# Y_Stepper_Motor_Driver.net
KiCad netlist of a schematic drawn in Altium Designer
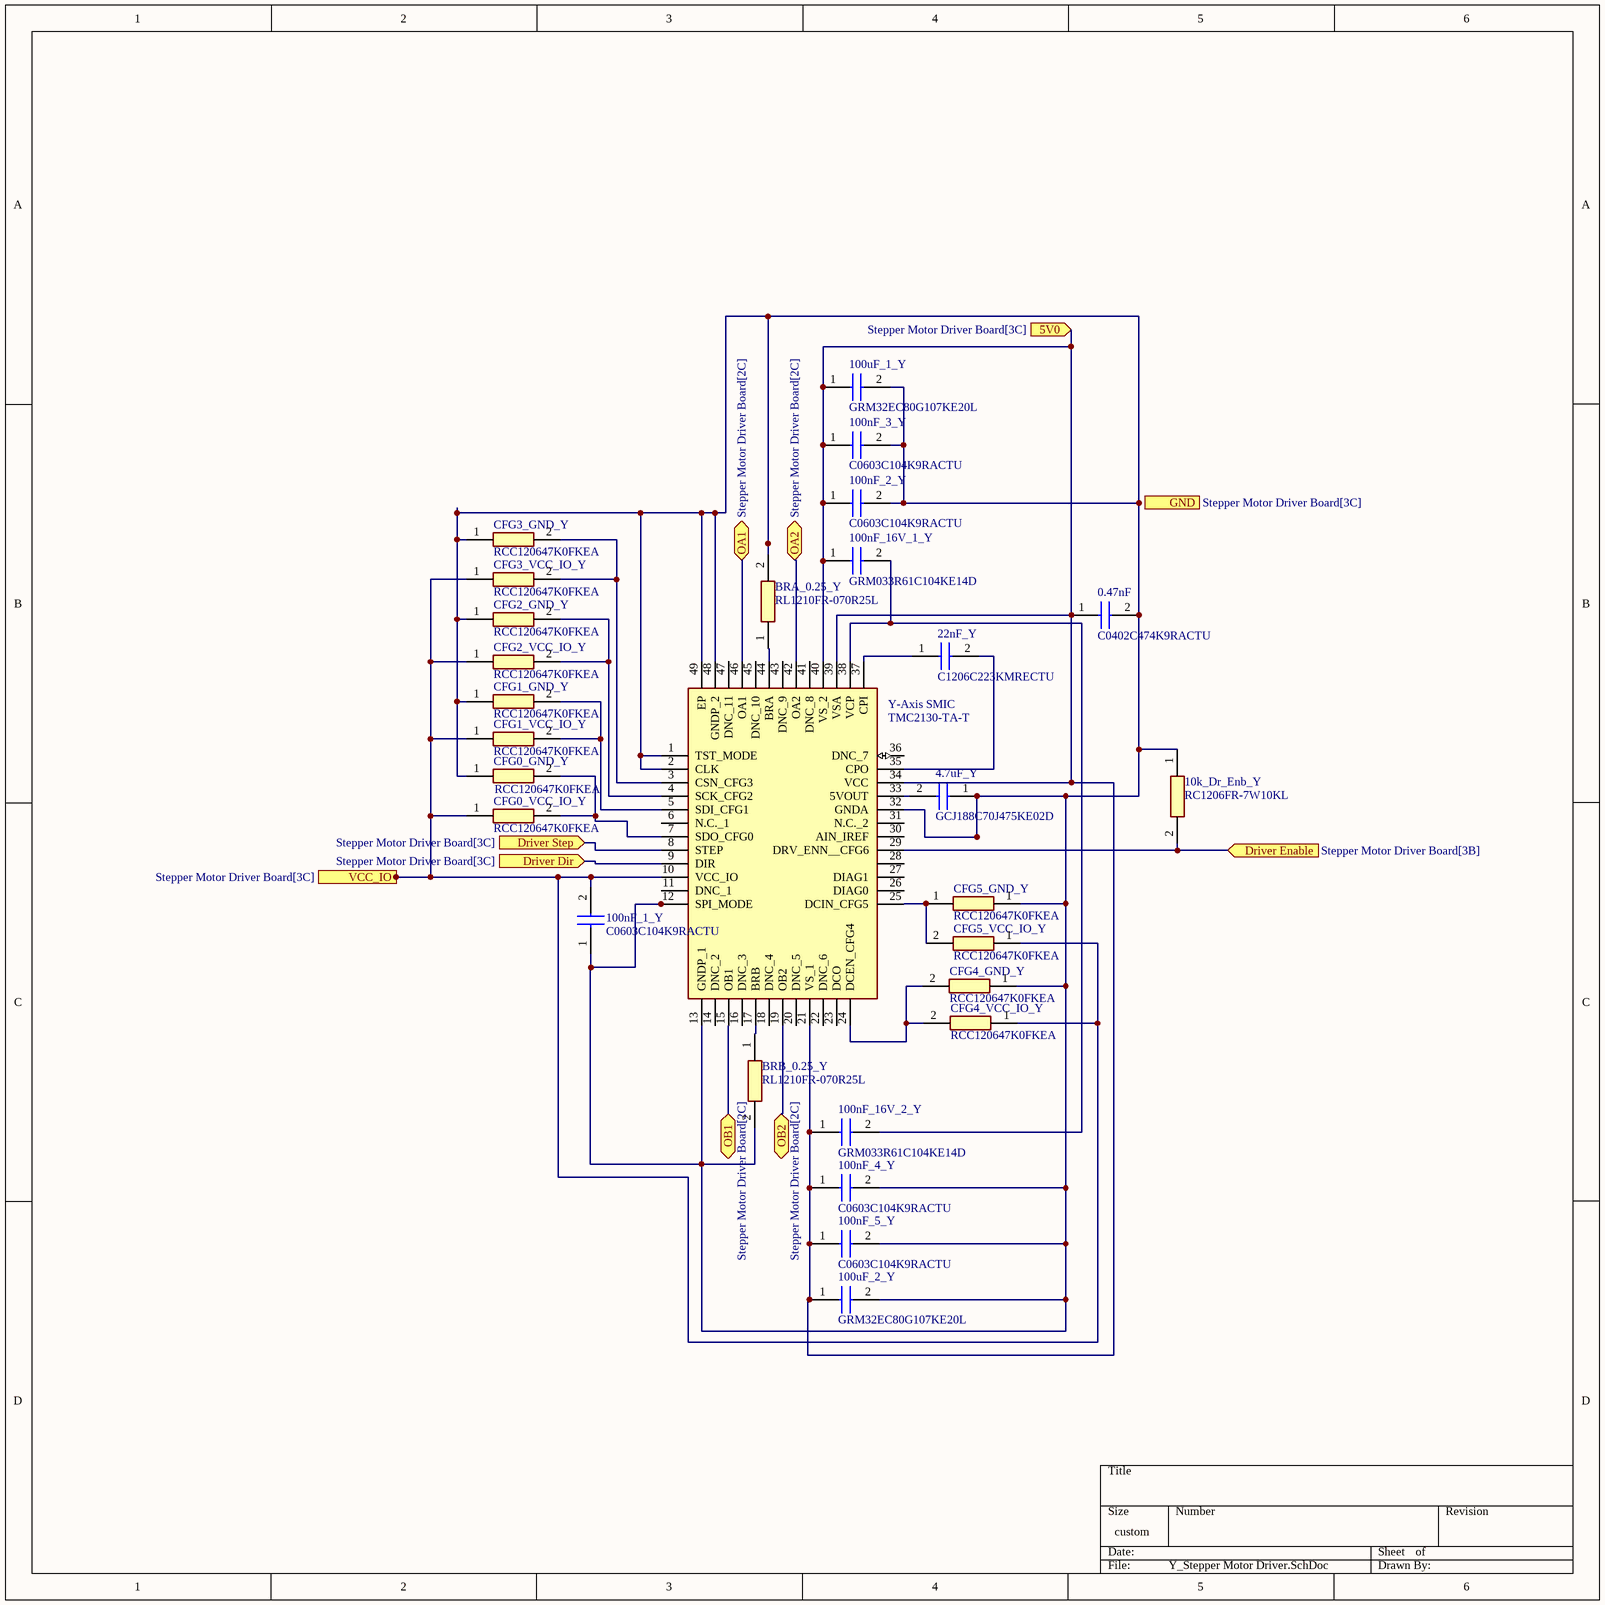
[diagram p0: Y_Stepper Motor Driver.SchDoc]

(export (version "E")
  (design (tool "Eeschema 10.0.6"))
  (components
    (comp (ref "0.47nF")
      (value "C0402C474K9RACTU")
      (footprint "SamacSys:CAPC1005X55N")
      (description "Capacitor")
      (fields (field (name "MOUSER PART NUMBER") "80-C0402C474K9RACTU"))
      (libsource (lib "*") (part "C0402C474K9RACTU"))
    )
    (comp (ref "4.7uF_Y")
      (value "GCJ188C70J475KE02D")
      (footprint "SamacSys:CAPC1608X100N")
      (description "Capacitor")
      (fields (field (name "MOUSER PART NUMBER") "81-GCJ188C70J475KE2D"))
      (libsource (lib "*") (part "GCJ188C70J475KE02D"))
    )
    (comp (ref "10k_Dr_Enb_Y")
      (value "RC1206FR-7W10KL")
      (footprint "SamacSys:RESC3116X65N")
      (description "Resistor")
      (libsource (lib "*") (part "RC1206FR-7W10KL"))
    )
    (comp (ref "22nF_Y")
      (value "C1206C223KMRECTU")
      (footprint "SamacSys:C1206")
      (description "Capacitor")
      (fields (field (name "MOUSER PART NUMBER") "80-C1206C223KMRECTU"))
      (libsource (lib "*") (part "C1206C223KMRECTU"))
    )
    (comp (ref "100nF_1_Y")
      (value "C0603C104K9RACTU")
      (footprint "SamacSys:C0603")
      (description "Capacitor")
      (fields (field (name "MOUSER PART NUMBER") "80-C0603C104K9R"))
      (libsource (lib "*") (part "C0603C104K9RACTU"))
    )
    (comp (ref "100nF_2_Y")
      (value "C0603C104K9RACTU")
      (footprint "SamacSys:C0603")
      (description "Capacitor")
      (fields (field (name "MOUSER PART NUMBER") "80-C0603C104K9R"))
      (libsource (lib "*") (part "C0603C104K9RACTU"))
    )
    (comp (ref "100nF_3_Y")
      (value "C0603C104K9RACTU")
      (footprint "SamacSys:C0603")
      (description "Capacitor")
      (fields (field (name "MOUSER PART NUMBER") "80-C0603C104K9R"))
      (libsource (lib "*") (part "C0603C104K9RACTU"))
    )
    (comp (ref "100nF_4_Y")
      (value "C0603C104K9RACTU")
      (footprint "SamacSys:C0603")
      (description "Capacitor")
      (fields (field (name "MOUSER PART NUMBER") "80-C0603C104K9R"))
      (libsource (lib "*") (part "C0603C104K9RACTU"))
    )
    (comp (ref "100nF_5_Y")
      (value "C0603C104K9RACTU")
      (footprint "SamacSys:C0603")
      (description "Capacitor")
      (fields (field (name "MOUSER PART NUMBER") "80-C0603C104K9R"))
      (libsource (lib "*") (part "C0603C104K9RACTU"))
    )
    (comp (ref "100nF_16V_1_Y")
      (value "GRM033R61C104KE14D")
      (footprint "SamacSys:CAPC0603X33N")
      (description "Capacitor")
      (fields (field (name "MOUSER PART NUMBER") "81-GRM033R61C104KE4D"))
      (libsource (lib "*") (part "GRM033R61C104KE14D"))
    )
    (comp (ref "100nF_16V_2_Y")
      (value "GRM033R61C104KE14D")
      (footprint "SamacSys:CAPC0603X33N")
      (description "Capacitor")
      (fields (field (name "MOUSER PART NUMBER") "81-GRM033R61C104KE4D"))
      (libsource (lib "*") (part "GRM033R61C104KE14D"))
    )
    (comp (ref "100uF_1_Y")
      (value "GRM32EC80G107KE20L")
      (footprint "SamacSys:CAPC3225X270N")
      (description "Capacitor")
      (fields (field (name "MOUSER PART NUMBER") "81-GRM32EC80G107KE0L"))
      (libsource (lib "*") (part "GRM32EC80G107KE20L"))
    )
    (comp (ref "100uF_2_Y")
      (value "GRM32EC80G107KE20L")
      (footprint "SamacSys:CAPC3225X270N")
      (description "Capacitor")
      (fields (field (name "MOUSER PART NUMBER") "81-GRM32EC80G107KE0L"))
      (libsource (lib "*") (part "GRM32EC80G107KE20L"))
    )
    (comp (ref "BRA_0.25_Y")
      (value "RL1210FR-070R25L")
      (footprint "SamacSys:RESC3126X65N")
      (description "Resistor")
      (fields (field (name "MOUSER PART NUMBER") "603-RL1210FR-070R25L"))
      (libsource (lib "") (part "RL1210FR-070R25L_1"))
    )
    (comp (ref "BRB_0.25_Y")
      (value "RL1210FR-070R25L")
      (footprint "SamacSys:RESC3126X65N")
      (description "Resistor")
      (fields (field (name "MOUSER PART NUMBER") "603-RL1210FR-070R25L"))
      (libsource (lib "*") (part "RL1210FR-070R25L"))
    )
    (comp (ref "CFG0_GND_Y")
      (value "RCC120647K0FKEA")
      (footprint "SamacSys:RCC1206_e3")
      (description "Resistor")
      (fields (field (name "MOUSER PART NUMBER") "71-RCC120647K0FKEA"))
      (libsource (lib "*") (part "RCC120647K0FKEA"))
    )
    (comp (ref "CFG0_VCC_IO_Y")
      (value "RCC120647K0FKEA")
      (footprint "SamacSys:RCC1206_e3")
      (description "Resistor")
      (fields (field (name "MOUSER PART NUMBER") "71-RCC120647K0FKEA"))
      (libsource (lib "*") (part "RCC120647K0FKEA"))
    )
    (comp (ref "CFG1_GND_Y")
      (value "RCC120647K0FKEA")
      (footprint "SamacSys:RCC1206_e3")
      (description "Resistor")
      (fields (field (name "MOUSER PART NUMBER") "71-RCC120647K0FKEA"))
      (libsource (lib "*") (part "RCC120647K0FKEA"))
    )
    (comp (ref "CFG1_VCC_IO_Y")
      (value "RCC120647K0FKEA")
      (footprint "SamacSys:RCC1206_e3")
      (description "Resistor")
      (fields (field (name "MOUSER PART NUMBER") "71-RCC120647K0FKEA"))
      (libsource (lib "*") (part "RCC120647K0FKEA"))
    )
    (comp (ref "CFG2_GND_Y")
      (value "RCC120647K0FKEA")
      (footprint "SamacSys:RCC1206_e3")
      (description "Resistor")
      (fields (field (name "MOUSER PART NUMBER") "71-RCC120647K0FKEA"))
      (libsource (lib "*") (part "RCC120647K0FKEA"))
    )
    (comp (ref "CFG2_VCC_IO_Y")
      (value "RCC120647K0FKEA")
      (footprint "SamacSys:RCC1206_e3")
      (description "Resistor")
      (fields (field (name "MOUSER PART NUMBER") "71-RCC120647K0FKEA"))
      (libsource (lib "*") (part "RCC120647K0FKEA"))
    )
    (comp (ref "CFG3_GND_Y")
      (value "RCC120647K0FKEA")
      (footprint "SamacSys:RCC1206_e3")
      (description "Resistor")
      (fields (field (name "MOUSER PART NUMBER") "71-RCC120647K0FKEA"))
      (libsource (lib "*") (part "RCC120647K0FKEA"))
    )
    (comp (ref "CFG3_VCC_IO_Y")
      (value "RCC120647K0FKEA")
      (footprint "SamacSys:RCC1206_e3")
      (description "Resistor")
      (fields (field (name "MOUSER PART NUMBER") "71-RCC120647K0FKEA"))
      (libsource (lib "*") (part "RCC120647K0FKEA"))
    )
    (comp (ref "CFG4_GND_Y")
      (value "RCC120647K0FKEA")
      (footprint "SamacSys:RCC1206_e3")
      (description "Resistor")
      (fields (field (name "MOUSER PART NUMBER") "71-RCC120647K0FKEA"))
      (libsource (lib "") (part "RCC120647K0FKEA_1"))
    )
    (comp (ref "CFG4_VCC_IO_Y")
      (value "RCC120647K0FKEA")
      (footprint "SamacSys:RCC1206_e3")
      (description "Resistor")
      (fields (field (name "MOUSER PART NUMBER") "71-RCC120647K0FKEA"))
      (libsource (lib "") (part "RCC120647K0FKEA_1"))
    )
    (comp (ref "CFG5_GND_Y")
      (value "RCC120647K0FKEA")
      (footprint "SamacSys:RCC1206_e3")
      (description "Resistor")
      (fields (field (name "MOUSER PART NUMBER") "71-RCC120647K0FKEA"))
      (libsource (lib "") (part "RCC120647K0FKEA_2"))
    )
    (comp (ref "CFG5_VCC_IO_Y")
      (value "RCC120647K0FKEA")
      (footprint "SamacSys:RCC1206_e3")
      (description "Resistor")
      (fields (field (name "MOUSER PART NUMBER") "71-RCC120647K0FKEA"))
      (libsource (lib "") (part "RCC120647K0FKEA_1"))
    )
    (comp (ref "Y-Axis SMIC")
      (value "TMC2130-TA-T")
      (footprint "SamacSys:QFP50P900X900X120-49N")
      (description "Integrated Circuit")
      (fields (field (name "MOUSER PART NUMBER") "700-TMC2130-TA-T"))
      (libsource (lib "*") (part "TMC2130-TA-T"))
    )
  )
  (nets
    (net (code "1") (name "/5V0") (class "Default")
      (node (ref "0.47nF") (pin "1") (pinfunction "1_1") (pintype "passive"))
      (node (ref "100nF_16V_1_Y") (pin "1") (pinfunction "1_1") (pintype "passive"))
      (node (ref "100nF_16V_2_Y") (pin "1") (pinfunction "1_1") (pintype "passive"))
      (node (ref "100nF_2_Y") (pin "1") (pinfunction "1_1") (pintype "passive"))
      (node (ref "100nF_3_Y") (pin "1") (pinfunction "1_1") (pintype "passive"))
      (node (ref "100nF_4_Y") (pin "1") (pinfunction "1_1") (pintype "passive"))
      (node (ref "100nF_5_Y") (pin "1") (pinfunction "1_1") (pintype "passive"))
      (node (ref "100uF_1_Y") (pin "1") (pinfunction "1_1") (pintype "passive"))
      (node (ref "100uF_2_Y") (pin "1") (pinfunction "1_1") (pintype "passive"))
      (node (ref "Y-Axis SMIC") (pin "21") (pinfunction "VS_1_21") (pintype "passive"))
      (node (ref "Y-Axis SMIC") (pin "34") (pinfunction "VCC_34") (pintype "passive"))
      (node (ref "Y-Axis SMIC") (pin "39") (pinfunction "VSA_39") (pintype "passive"))
      (node (ref "Y-Axis SMIC") (pin "40") (pinfunction "VS_2_40") (pintype "passive"))
    )
    (net (code "2") (name "/Driver Dir") (class "Default")
      (node (ref "Y-Axis SMIC") (pin "9") (pinfunction "DIR_9") (pintype "passive"))
    )
    (net (code "3") (name "/Driver Enable") (class "Default")
      (node (ref "10k_Dr_Enb_Y") (pin "2") (pinfunction "2_2") (pintype "passive"))
      (node (ref "Y-Axis SMIC") (pin "29") (pinfunction "DRV_ENN__CFG6_29") (pintype "passive"))
    )
    (net (code "4") (name "/Driver Step") (class "Default")
      (node (ref "Y-Axis SMIC") (pin "8") (pinfunction "STEP_8") (pintype "passive"))
    )
    (net (code "6") (name "/OA1") (class "Default")
      (node (ref "Y-Axis SMIC") (pin "46") (pinfunction "OA1_46") (pintype "passive"))
    )
    (net (code "7") (name "/OA2") (class "Default")
      (node (ref "Y-Axis SMIC") (pin "42") (pinfunction "OA2_42") (pintype "passive"))
    )
    (net (code "8") (name "/OB1") (class "Default")
      (node (ref "Y-Axis SMIC") (pin "15") (pinfunction "OB1_15") (pintype "passive"))
    )
    (net (code "9") (name "/OB2") (class "Default")
      (node (ref "Y-Axis SMIC") (pin "19") (pinfunction "OB2_19") (pintype "passive"))
    )
    (net (code "10") (name "/VCC_IO") (class "Default")
      (node (ref "100nF_1_Y") (pin "2") (pinfunction "2_2") (pintype "passive"))
      (node (ref "CFG0_VCC_IO_Y") (pin "1") (pinfunction "1_1") (pintype "passive"))
      (node (ref "CFG1_VCC_IO_Y") (pin "1") (pinfunction "1_1") (pintype "passive"))
      (node (ref "CFG2_VCC_IO_Y") (pin "1") (pinfunction "1_1") (pintype "passive"))
      (node (ref "CFG3_VCC_IO_Y") (pin "1") (pinfunction "1_1") (pintype "passive"))
      (node (ref "CFG4_VCC_IO_Y") (pin "1") (pinfunction "1_1") (pintype "passive"))
      (node (ref "CFG5_VCC_IO_Y") (pin "1") (pinfunction "1_1") (pintype "passive"))
      (node (ref "Y-Axis SMIC") (pin "10") (pinfunction "VCC_IO_10") (pintype "passive"))
    )
    (net (code "11") (name "Net-(Y-Axis SMIC-5VOUT)") (class "Default")
      (node (ref "4.7uF_Y") (pin "2") (pinfunction "2_2") (pintype "passive"))
      (node (ref "Y-Axis SMIC") (pin "33") (pinfunction "5VOUT_33") (pintype "passive"))
    )
    (net (code "12") (name "Net-(Y-Axis SMIC-BRA)") (class "Default")
      (node (ref "BRA_0.25_Y") (pin "1") (pinfunction "1_1") (pintype "passive"))
      (node (ref "Y-Axis SMIC") (pin "44") (pinfunction "BRA_44") (pintype "passive"))
    )
    (net (code "13") (name "Net-(Y-Axis SMIC-BRB)") (class "Default")
      (node (ref "BRB_0.25_Y") (pin "1") (pinfunction "1_1") (pintype "passive"))
      (node (ref "Y-Axis SMIC") (pin "17") (pinfunction "BRB_17") (pintype "passive"))
    )
    (net (code "14") (name "Net-(Y-Axis SMIC-CLK)") (class "Default")
      (node (ref "0.47nF") (pin "2") (pinfunction "2_2") (pintype "passive"))
      (node (ref "100nF_1_Y") (pin "1") (pinfunction "1_1") (pintype "passive"))
      (node (ref "100nF_2_Y") (pin "2") (pinfunction "2_2") (pintype "passive"))
      (node (ref "100nF_3_Y") (pin "2") (pinfunction "2_2") (pintype "passive"))
      (node (ref "100nF_4_Y") (pin "2") (pinfunction "2_2") (pintype "passive"))
      (node (ref "100nF_5_Y") (pin "2") (pinfunction "2_2") (pintype "passive"))
      (node (ref "100uF_1_Y") (pin "2") (pinfunction "2_2") (pintype "passive"))
      (node (ref "100uF_2_Y") (pin "2") (pinfunction "2_2") (pintype "passive"))
      (node (ref "10k_Dr_Enb_Y") (pin "1") (pinfunction "1_1") (pintype "passive"))
      (node (ref "4.7uF_Y") (pin "1") (pinfunction "1_1") (pintype "passive"))
      (node (ref "BRA_0.25_Y") (pin "2") (pinfunction "2_2") (pintype "passive"))
      (node (ref "BRB_0.25_Y") (pin "2") (pinfunction "2_2") (pintype "passive"))
      (node (ref "CFG0_GND_Y") (pin "1") (pinfunction "1_1") (pintype "passive"))
      (node (ref "CFG1_GND_Y") (pin "1") (pinfunction "1_1") (pintype "passive"))
      (node (ref "CFG2_GND_Y") (pin "1") (pinfunction "1_1") (pintype "passive"))
      (node (ref "CFG3_GND_Y") (pin "1") (pinfunction "1_1") (pintype "passive"))
      (node (ref "CFG4_GND_Y") (pin "1") (pinfunction "1_1") (pintype "passive"))
      (node (ref "CFG5_GND_Y") (pin "1") (pinfunction "1_1") (pintype "passive"))
      (node (ref "Y-Axis SMIC") (pin "1") (pinfunction "TST_MODE_1") (pintype "passive"))
      (node (ref "Y-Axis SMIC") (pin "12") (pinfunction "SPI_MODE_12") (pintype "passive"))
      (node (ref "Y-Axis SMIC") (pin "13") (pinfunction "GNDP_1_13") (pintype "passive"))
      (node (ref "Y-Axis SMIC") (pin "2") (pinfunction "CLK_2") (pintype "passive"))
      (node (ref "Y-Axis SMIC") (pin "32") (pinfunction "GNDA_32") (pintype "passive"))
      (node (ref "Y-Axis SMIC") (pin "48") (pinfunction "GNDP_2_48") (pintype "passive"))
      (node (ref "Y-Axis SMIC") (pin "49") (pinfunction "EP_49") (pintype "passive"))
    )
    (net (code "15") (name "Net-(Y-Axis SMIC-CPI)") (class "Default")
      (node (ref "22nF_Y") (pin "1") (pinfunction "1_1") (pintype "passive"))
      (node (ref "Y-Axis SMIC") (pin "37") (pinfunction "CPI_37") (pintype "passive"))
    )
    (net (code "16") (name "Net-(Y-Axis SMIC-CPO)") (class "Default")
      (node (ref "22nF_Y") (pin "2") (pinfunction "2_2") (pintype "passive"))
      (node (ref "Y-Axis SMIC") (pin "35") (pinfunction "CPO_35") (pintype "passive"))
    )
    (net (code "17") (name "Net-(Y-Axis SMIC-CSN_CFG3)") (class "Default")
      (node (ref "CFG3_GND_Y") (pin "2") (pinfunction "2_2") (pintype "passive"))
      (node (ref "CFG3_VCC_IO_Y") (pin "2") (pinfunction "2_2") (pintype "passive"))
      (node (ref "Y-Axis SMIC") (pin "3") (pinfunction "CSN_CFG3_3") (pintype "passive"))
    )
    (net (code "18") (name "Net-(Y-Axis SMIC-DCEN_CFG4)") (class "Default")
      (node (ref "CFG4_GND_Y") (pin "2") (pinfunction "2_2") (pintype "passive"))
      (node (ref "CFG4_VCC_IO_Y") (pin "2") (pinfunction "2_2") (pintype "passive"))
      (node (ref "Y-Axis SMIC") (pin "24") (pinfunction "DCEN_CFG4_24") (pintype "passive"))
    )
    (net (code "19") (name "Net-(Y-Axis SMIC-DCIN_CFG5)") (class "Default")
      (node (ref "CFG5_GND_Y") (pin "1") (pinfunction "1_1") (pintype "passive"))
      (node (ref "CFG5_VCC_IO_Y") (pin "2") (pinfunction "2_2") (pintype "passive"))
      (node (ref "Y-Axis SMIC") (pin "25") (pinfunction "DCIN_CFG5_25") (pintype "passive"))
    )
    (net (code "20") (name "Net-(Y-Axis SMIC-SCK_CFG2)") (class "Default")
      (node (ref "CFG2_GND_Y") (pin "2") (pinfunction "2_2") (pintype "passive"))
      (node (ref "CFG2_VCC_IO_Y") (pin "2") (pinfunction "2_2") (pintype "passive"))
      (node (ref "Y-Axis SMIC") (pin "4") (pinfunction "SCK_CFG2_4") (pintype "passive"))
    )
    (net (code "21") (name "Net-(Y-Axis SMIC-SDI_CFG1)") (class "Default")
      (node (ref "CFG1_GND_Y") (pin "2") (pinfunction "2_2") (pintype "passive"))
      (node (ref "CFG1_VCC_IO_Y") (pin "2") (pinfunction "2_2") (pintype "passive"))
      (node (ref "Y-Axis SMIC") (pin "5") (pinfunction "SDI_CFG1_5") (pintype "passive"))
    )
    (net (code "22") (name "Net-(Y-Axis SMIC-SDO_CFG0)") (class "Default")
      (node (ref "CFG0_GND_Y") (pin "2") (pinfunction "2_2") (pintype "passive"))
      (node (ref "CFG0_VCC_IO_Y") (pin "2") (pinfunction "2_2") (pintype "passive"))
      (node (ref "Y-Axis SMIC") (pin "7") (pinfunction "SDO_CFG0_7") (pintype "passive"))
    )
    (net (code "23") (name "Net-(Y-Axis SMIC-VCP)") (class "Default")
      (node (ref "100nF_16V_1_Y") (pin "2") (pinfunction "2_2") (pintype "passive"))
      (node (ref "100nF_16V_2_Y") (pin "2") (pinfunction "2_2") (pintype "passive"))
      (node (ref "Y-Axis SMIC") (pin "38") (pinfunction "VCP_38") (pintype "passive"))
    )
    (net (code "24") (name "unconnected-(Y-Axis SMIC-AIN_IREF-Pad30)") (class "Default")
      (node (ref "Y-Axis SMIC") (pin "30") (pinfunction "AIN_IREF_30") (pintype "passive"))
    )
    (net (code "25") (name "unconnected-(Y-Axis SMIC-DCO-Pad23)") (class "Default")
      (node (ref "Y-Axis SMIC") (pin "23") (pinfunction "DCO_23") (pintype "passive"))
    )
    (net (code "26") (name "unconnected-(Y-Axis SMIC-DIAG0-Pad26)") (class "Default")
      (node (ref "Y-Axis SMIC") (pin "26") (pinfunction "DIAG0_26") (pintype "passive"))
    )
    (net (code "27") (name "unconnected-(Y-Axis SMIC-DIAG1-Pad27)") (class "Default")
      (node (ref "Y-Axis SMIC") (pin "27") (pinfunction "DIAG1_27") (pintype "passive"))
    )
    (net (code "28") (name "unconnected-(Y-Axis SMIC-DNC_1-Pad11)") (class "Default")
      (node (ref "Y-Axis SMIC") (pin "11") (pinfunction "DNC_1_11") (pintype "passive"))
    )
    (net (code "29") (name "unconnected-(Y-Axis SMIC-DNC_2-Pad14)") (class "Default")
      (node (ref "Y-Axis SMIC") (pin "14") (pinfunction "DNC_2_14") (pintype "passive"))
    )
    (net (code "30") (name "unconnected-(Y-Axis SMIC-DNC_3-Pad16)") (class "Default")
      (node (ref "Y-Axis SMIC") (pin "16") (pinfunction "DNC_3_16") (pintype "passive"))
    )
    (net (code "31") (name "unconnected-(Y-Axis SMIC-DNC_4-Pad18)") (class "Default")
      (node (ref "Y-Axis SMIC") (pin "18") (pinfunction "DNC_4_18") (pintype "passive"))
    )
    (net (code "32") (name "unconnected-(Y-Axis SMIC-DNC_5-Pad20)") (class "Default")
      (node (ref "Y-Axis SMIC") (pin "20") (pinfunction "DNC_5_20") (pintype "passive"))
    )
    (net (code "33") (name "unconnected-(Y-Axis SMIC-DNC_6-Pad22)") (class "Default")
      (node (ref "Y-Axis SMIC") (pin "22") (pinfunction "DNC_6_22") (pintype "passive"))
    )
    (net (code "34") (name "unconnected-(Y-Axis SMIC-DNC_7-Pad28)") (class "Default")
      (node (ref "Y-Axis SMIC") (pin "28") (pinfunction "DNC_7_28") (pintype "passive"))
    )
    (net (code "35") (name "unconnected-(Y-Axis SMIC-DNC_7-Pad36)") (class "Default")
      (node (ref "Y-Axis SMIC") (pin "36") (pinfunction "DNC_7_36") (pintype "bidirectional"))
    )
    (net (code "36") (name "unconnected-(Y-Axis SMIC-DNC_8-Pad41)") (class "Default")
      (node (ref "Y-Axis SMIC") (pin "41") (pinfunction "DNC_8_41") (pintype "passive"))
    )
    (net (code "37") (name "unconnected-(Y-Axis SMIC-DNC_9-Pad43)") (class "Default")
      (node (ref "Y-Axis SMIC") (pin "43") (pinfunction "DNC_9_43") (pintype "passive"))
    )
    (net (code "38") (name "unconnected-(Y-Axis SMIC-DNC_10-Pad45)") (class "Default")
      (node (ref "Y-Axis SMIC") (pin "45") (pinfunction "DNC_10_45") (pintype "passive"))
    )
    (net (code "39") (name "unconnected-(Y-Axis SMIC-DNC_11-Pad47)") (class "Default")
      (node (ref "Y-Axis SMIC") (pin "47") (pinfunction "DNC_11_47") (pintype "passive"))
    )
    (net (code "40") (name "unconnected-(Y-Axis SMIC-N.C._1-Pad6)") (class "Default")
      (node (ref "Y-Axis SMIC") (pin "6") (pinfunction "N.C._1_6") (pintype "passive"))
    )
    (net (code "41") (name "unconnected-(Y-Axis SMIC-N.C._2-Pad31)") (class "Default")
      (node (ref "Y-Axis SMIC") (pin "31") (pinfunction "N.C._2_31") (pintype "passive"))
    )
  )
)
